# 2_PSU.net
KiCad netlist of a schematic drawn in Altium Designer
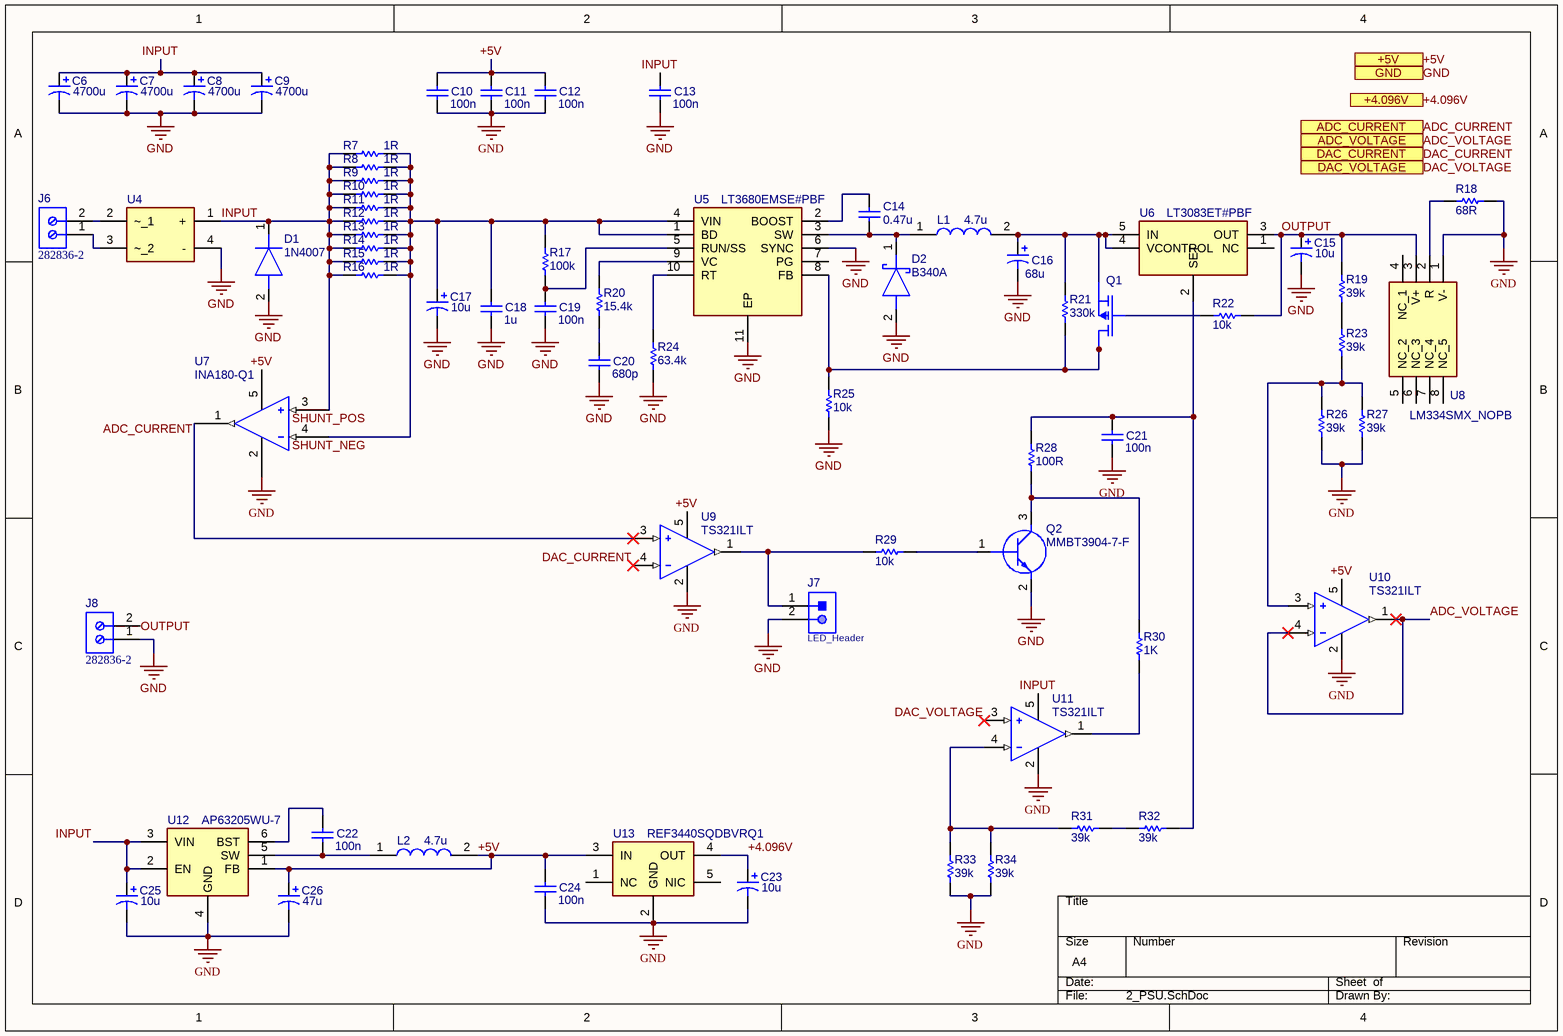
[diagram p0: 2_PSU.SchDoc]

(export (version "E")
  (design (tool "Eeschema 10.0.6"))
  (components
    (comp (ref "C6")
      (value "4700u")
      (footprint "CAPPRD750W80D1850H4150")
      (description "Polarized Capacitor (Radial)")
      (fields (field (name "Comment") "Cap Pol1") (field (name "PUBLISHER") "Altium Limited"))
      (libsource (lib "Miscellaneous Devices") (part "Cap Pol1"))
    )
    (comp (ref "C7")
      (value "4700u")
      (footprint "CAPPRD750W80D1850H4150")
      (description "Polarized Capacitor (Radial)")
      (fields (field (name "Comment") "Cap Pol1") (field (name "PUBLISHER") "Altium Limited"))
      (libsource (lib "Miscellaneous Devices") (part "Cap Pol1"))
    )
    (comp (ref "C8")
      (value "4700u")
      (footprint "CAPPRD750W80D1850H4150")
      (description "Polarized Capacitor (Radial)")
      (fields (field (name "Comment") "Cap Pol1") (field (name "PUBLISHER") "Altium Limited"))
      (libsource (lib "Miscellaneous Devices") (part "Cap Pol1"))
    )
    (comp (ref "C9")
      (value "4700u")
      (footprint "CAPPRD750W80D1850H4150")
      (description "Polarized Capacitor (Radial)")
      (fields (field (name "Comment") "Cap Pol1") (field (name "PUBLISHER") "Altium Limited"))
      (libsource (lib "Miscellaneous Devices") (part "Cap Pol1"))
    )
    (comp (ref "C10")
      (value "100n")
      (footprint "6-0805_N")
      (description "Capacitor")
      (libsource (lib "Simulation Generic Components") (part "Capacitor"))
    )
    (comp (ref "C11")
      (value "100n")
      (footprint "6-0805_N")
      (description "Capacitor")
      (libsource (lib "Simulation Generic Components") (part "Capacitor"))
    )
    (comp (ref "C12")
      (value "100n")
      (footprint "6-0805_N")
      (description "Capacitor")
      (libsource (lib "Simulation Generic Components") (part "Capacitor"))
    )
    (comp (ref "C13")
      (value "100n")
      (footprint "6-0805_N")
      (description "Capacitor")
      (libsource (lib "Simulation Generic Components") (part "Capacitor"))
    )
    (comp (ref "C14")
      (value "0.47u")
      (footprint "6-0805_N")
      (description "Capacitor")
      (libsource (lib "Simulation Generic Components") (part "Capacitor"))
    )
    (comp (ref "C15")
      (value "10u")
      (footprint "CAPPRD200W52D500H1250")
      (description "Polarized Capacitor (Radial)")
      (fields (field (name "Comment") "Cap Pol1") (field (name "PUBLISHER") "Altium Limited"))
      (libsource (lib "Miscellaneous Devices") (part "Cap Pol1"))
    )
    (comp (ref "C16")
      (value "68u")
      (footprint "CAPPRD250W52D630H1100")
      (description "Polarized Capacitor (Radial)")
      (fields (field (name "Comment") "Cap Pol1") (field (name "PUBLISHER") "Altium Limited"))
      (libsource (lib "Miscellaneous Devices") (part "Cap Pol1"))
    )
    (comp (ref "C17")
      (value "10u")
      (footprint "CAPPRD200W52D500H1250")
      (description "Polarized Capacitor (Radial)")
      (fields (field (name "Comment") "Cap Pol1") (field (name "PUBLISHER") "Altium Limited"))
      (libsource (lib "Miscellaneous Devices") (part "Cap Pol1"))
    )
    (comp (ref "C18")
      (value "1u")
      (footprint "6-0805_N")
      (description "Capacitor")
      (libsource (lib "Simulation Generic Components") (part "Capacitor"))
    )
    (comp (ref "C19")
      (value "100n")
      (footprint "6-0805_N")
      (description "Capacitor")
      (libsource (lib "Simulation Generic Components") (part "Capacitor"))
    )
    (comp (ref "C20")
      (value "680p")
      (footprint "6-0805_N")
      (description "Capacitor")
      (libsource (lib "Simulation Generic Components") (part "Capacitor"))
    )
    (comp (ref "C21")
      (value "100n")
      (footprint "6-0805_N")
      (description "Capacitor")
      (libsource (lib "Simulation Generic Components") (part "Capacitor"))
    )
    (comp (ref "C22")
      (value "100n")
      (footprint "6-0805_N")
      (description "Capacitor")
      (libsource (lib "Simulation Generic Components") (part "Capacitor"))
    )
    (comp (ref "C23")
      (value "10u")
      (footprint "CAPPRD200W52D500H1250")
      (description "Polarized Capacitor (Radial)")
      (fields (field (name "Comment") "Cap Pol1") (field (name "PUBLISHER") "Altium Limited"))
      (libsource (lib "Miscellaneous Devices") (part "Cap Pol1"))
    )
    (comp (ref "C24")
      (value "100n")
      (footprint "6-0805_N")
      (description "Capacitor")
      (libsource (lib "Simulation Generic Components") (part "Capacitor"))
    )
    (comp (ref "C25")
      (value "10u")
      (footprint "CAPPRD200W52D500H1250")
      (description "Polarized Capacitor (Radial)")
      (fields (field (name "Comment") "Cap Pol1") (field (name "PUBLISHER") "Altium Limited"))
      (libsource (lib "Miscellaneous Devices") (part "Cap Pol1"))
    )
    (comp (ref "C26")
      (value "47u")
      (footprint "CAPPRD200W52D500H1250")
      (description "Polarized Capacitor (Radial)")
      (fields (field (name "Comment") "Cap Pol1") (field (name "PUBLISHER") "Altium Limited"))
      (libsource (lib "Miscellaneous Devices") (part "Cap Pol1"))
    )
    (comp (ref "D1")
      (value "1N4007")
      (footprint "DIOAD1405W58L465D235")
      (description "Diode")
      (fields (field (name "MOUSER PART NUMBER") "637-1N4007"))
      (libsource (lib "PowerSupplyPE") (part "1N4007"))
    )
    (comp (ref "D2")
      (value "B340A")
      (footprint "DIOM5127X229N")
      (description "Diode")
      (fields
        (field (name "MANUFACTURER_PART_NUMBER") "B340A-E3/61T")
        (field (name "MOUSER PART NUMBER") "625-BD340A-E3/61T")
      )
      (libsource (lib "PowerSupplyPE") (part "B340A-E3_61T"))
    )
    (comp (ref "J6")
      (value "282836-2")
      (footprint "TECO-282836-2_V")
      (description "Female Header, Pitch 5 mm, 1 x 2 Position, Height 10 mm, Tail Length 3.5 mm, Rohs, Bulk")
      (fields (field (name "VOLTAGE") "300V") (field (name "MANUFACTURER") "TE Connectivity"))
      (libsource (lib "Altium Content Vault") (part "CN-1P-F-TB2"))
    )
    (comp (ref "J7")
      (value "LED_Header")
      (footprint "61300211121")
      (description "THT Vertical Pin Header WR-PHD, Pitch 2.54 mm, Single Row, 2 pins")
      (fields
        (field (name "MANUFACTURER") "Wurth Elektronik")
        (field (name "PART NUMBER") "61300211121")
        (field (name "PUBLISHER") "WurthElektronik")
      )
      (libsource (lib "Altium Content Vault") (part "WE-CN-1P-M-R2"))
    )
    (comp (ref "J8")
      (value "282836-2")
      (footprint "TECO-282836-2_V")
      (description "Female Header, Pitch 5 mm, 1 x 2 Position, Height 10 mm, Tail Length 3.5 mm, Rohs, Bulk")
      (fields (field (name "VOLTAGE") "300V") (field (name "MANUFACTURER") "TE Connectivity"))
      (libsource (lib "Altium Content Vault") (part "CN-1P-F-TB2"))
    )
    (comp (ref "L1")
      (value "4.7u")
      (footprint "VLS5045EX330M")
      (description "Inductor")
      (fields
        (field (name "MANUFACTURER_PART_NUMBER") "VLS5045EX-4R7M-H")
        (field (name "MOUSER PART NUMBER") "810-VLS5045EX-4R7M-H")
      )
      (libsource (lib "PowerSupplyPE") (part "VLS5045EX-4R7M-H"))
    )
    (comp (ref "L2")
      (value "4.7u")
      (footprint "VLS5045EX330M")
      (description "Inductor")
      (fields
        (field (name "MANUFACTURER_PART_NUMBER") "VLS5045EX-4R7M-H")
        (field (name "MOUSER PART NUMBER") "810-VLS5045EX-4R7M-H")
      )
      (libsource (lib "PowerSupplyPE") (part "VLS5045EX-4R7M-H"))
    )
    (comp (ref "Q1")
      (value "ZVP4525GTA")
      (footprint "SOT230P700X180-4N")
      (description "MOSFET (P-Channel)")
      (fields (field (name "MOUSER PART NUMBER") "522-ZVP4525GTA"))
      (libsource (lib "PowerSupplyPE") (part "ZVP4525GTA"))
    )
    (comp (ref "Q2")
      (value "MMBT3904-7-F")
      (footprint "SOT96P240X110-3N")
      (description "Transistor BJT NPN")
      (fields (field (name "MOUSER PART NUMBER") "621-MMBT3904-F"))
      (libsource (lib "*") (part "MMBT3904-7-F"))
    )
    (comp (ref "R7")
      (value "1R")
      (footprint "6-0805_N")
      (description "Resistor")
      (libsource (lib "Simulation Generic Components") (part "Resistor"))
    )
    (comp (ref "R8")
      (value "1R")
      (footprint "6-0805_N")
      (description "Resistor")
      (libsource (lib "Simulation Generic Components") (part "Resistor"))
    )
    (comp (ref "R9")
      (value "1R")
      (footprint "6-0805_N")
      (description "Resistor")
      (libsource (lib "Simulation Generic Components") (part "Resistor"))
    )
    (comp (ref "R10")
      (value "1R")
      (footprint "6-0805_N")
      (description "Resistor")
      (libsource (lib "Simulation Generic Components") (part "Resistor"))
    )
    (comp (ref "R11")
      (value "1R")
      (footprint "6-0805_N")
      (description "Resistor")
      (libsource (lib "Simulation Generic Components") (part "Resistor"))
    )
    (comp (ref "R12")
      (value "1R")
      (footprint "6-0805_N")
      (description "Resistor")
      (libsource (lib "Simulation Generic Components") (part "Resistor"))
    )
    (comp (ref "R13")
      (value "1R")
      (footprint "6-0805_N")
      (description "Resistor")
      (libsource (lib "Simulation Generic Components") (part "Resistor"))
    )
    (comp (ref "R14")
      (value "1R")
      (footprint "6-0805_N")
      (description "Resistor")
      (libsource (lib "Simulation Generic Components") (part "Resistor"))
    )
    (comp (ref "R15")
      (value "1R")
      (footprint "6-0805_N")
      (description "Resistor")
      (libsource (lib "Simulation Generic Components") (part "Resistor"))
    )
    (comp (ref "R16")
      (value "1R")
      (footprint "6-0805_N")
      (description "Resistor")
      (libsource (lib "Simulation Generic Components") (part "Resistor"))
    )
    (comp (ref "R17")
      (value "100k")
      (footprint "6-0805_N")
      (description "Resistor")
      (libsource (lib "Simulation Generic Components") (part "Resistor"))
    )
    (comp (ref "R18")
      (value "68R")
      (footprint "6-0805_N")
      (description "Resistor")
      (libsource (lib "Simulation Generic Components") (part "Resistor"))
    )
    (comp (ref "R19")
      (value "39k")
      (footprint "6-0805_N")
      (description "Resistor")
      (libsource (lib "Simulation Generic Components") (part "Resistor"))
    )
    (comp (ref "R20")
      (value "15.4k")
      (footprint "6-0805_N")
      (description "Resistor")
      (libsource (lib "Simulation Generic Components") (part "Resistor"))
    )
    (comp (ref "R21")
      (value "330k")
      (footprint "6-0805_N")
      (description "Resistor")
      (libsource (lib "Simulation Generic Components") (part "Resistor"))
    )
    (comp (ref "R22")
      (value "10k")
      (footprint "6-0805_N")
      (description "Resistor")
      (libsource (lib "Simulation Generic Components") (part "Resistor"))
    )
    (comp (ref "R23")
      (value "39k")
      (footprint "6-0805_N")
      (description "Resistor")
      (libsource (lib "Simulation Generic Components") (part "Resistor"))
    )
    (comp (ref "R24")
      (value "63.4k")
      (footprint "6-0805_N")
      (description "Resistor")
      (libsource (lib "Simulation Generic Components") (part "Resistor"))
    )
    (comp (ref "R25")
      (value "10k")
      (footprint "6-0805_N")
      (description "Resistor")
      (libsource (lib "Simulation Generic Components") (part "Resistor"))
    )
    (comp (ref "R26")
      (value "39k")
      (footprint "6-0805_N")
      (description "Resistor")
      (libsource (lib "Simulation Generic Components") (part "Resistor"))
    )
    (comp (ref "R27")
      (value "39k")
      (footprint "6-0805_N")
      (description "Resistor")
      (libsource (lib "Simulation Generic Components") (part "Resistor"))
    )
    (comp (ref "R28")
      (value "100R")
      (footprint "6-0805_N")
      (description "Resistor")
      (libsource (lib "Simulation Generic Components") (part "Resistor"))
    )
    (comp (ref "R29")
      (value "10k")
      (footprint "6-0805_N")
      (description "Resistor")
      (libsource (lib "Simulation Generic Components") (part "Resistor"))
    )
    (comp (ref "R30")
      (value "1K")
      (footprint "6-0805_N")
      (description "Resistor")
      (libsource (lib "Simulation Generic Components") (part "Resistor"))
    )
    (comp (ref "R31")
      (value "39k")
      (footprint "6-0805_N")
      (description "Resistor")
      (libsource (lib "Simulation Generic Components") (part "Resistor"))
    )
    (comp (ref "R32")
      (value "39k")
      (footprint "6-0805_N")
      (description "Resistor")
      (libsource (lib "Simulation Generic Components") (part "Resistor"))
    )
    (comp (ref "R33")
      (value "39k")
      (footprint "6-0805_N")
      (description "Resistor")
      (libsource (lib "Simulation Generic Components") (part "Resistor"))
    )
    (comp (ref "R34")
      (value "39k")
      (footprint "6-0805_N")
      (description "Resistor")
      (libsource (lib "Simulation Generic Components") (part "Resistor"))
    )
    (comp (ref "U4")
      (value "GBU1010_T0_00601")
      (footprint "GBU1010_T0_00601")
      (description "Bridge Rectifier")
      (fields (field (name "MOUSER PART NUMBER") "241-GBU1010_T0_00601"))
      (libsource (lib "PowerSupplyPE") (part "GBU1010_T0_00601"))
    )
    (comp (ref "U5")
      (value "LT3680EMSE#PBF")
      (footprint "SOP50P490X110-11N")
      (description "Integrated Circuit")
      (fields (field (name "MOUSER PART NUMBER") "584-LT3680EMSE#PBF"))
      (libsource (lib "PowerSupplyPE") (part "LT3680EMSE#PBF"))
    )
    (comp (ref "U6")
      (value "LT3083ET#PBF")
      (footprint "TO170P457X1022X2306-5P")
      (description "Integrated Circuit")
      (fields (field (name "MOUSER PART NUMBER") "584-LT3083ET#PBF"))
      (libsource (lib "PowerSupplyPE") (part "LT3083ET#PBF"))
    )
    (comp (ref "U7")
      (value "INA180-Q1")
      (footprint "SOT95P280X145-5N")
      (description "Current Sense Amplifier")
      (libsource (lib "PowerSupplyPE") (part "INA180-Q1"))
    )
    (comp (ref "U8")
      (value "LM334SMX_NOPB")
      (footprint "SOIC127P600X175-8N")
      (description "Integrated Circuit")
      (fields
        (field (name "MANUFACTURER_PART_NUMBER") "LM334SMX/NOPB")
        (field (name "MOUSER PART NUMBER") "926-LM334SMX/NOPB")
      )
      (libsource (lib "PowerSupplyPE") (part "LM334SMX_NOPB"))
    )
    (comp (ref "U9")
      (value "TS321ILT")
      (footprint "SOT95P280X145-5N")
      (description "Integrated Circuit")
      (fields (field (name "MOUSER PART NUMBER") "511-TS321IL"))
      (libsource (lib "PowerSupplyPE") (part "TS321ILT"))
    )
    (comp (ref "U10")
      (value "TS321ILT")
      (footprint "SOT95P280X145-5N")
      (description "Integrated Circuit")
      (fields (field (name "MOUSER PART NUMBER") "511-TS321IL"))
      (libsource (lib "PowerSupplyPE") (part "TS321ILT"))
    )
    (comp (ref "U11")
      (value "TS321ILT")
      (footprint "SOT95P280X145-5N")
      (description "Integrated Circuit")
      (fields (field (name "MOUSER PART NUMBER") "511-TS321IL"))
      (libsource (lib "PowerSupplyPE") (part "TS321ILT"))
    )
    (comp (ref "U12")
      (value "AP63205WU-7")
      (footprint "SOT95P280X100-6N")
      (description "Integrated Circuit")
      (fields (field (name "MOUSER PART NUMBER") "621-AP63205WU-7"))
      (libsource (lib "PowerSupplyPE") (part "AP63205WU-7"))
    )
    (comp (ref "U13")
      (value "REF3440SQDBVRQ1")
      (footprint "SOT95P280X145-5N")
      (description "Integrated Circuit")
      (fields (field (name "MOUSER PART NUMBER") "595-REF3440SQDBVRQ1"))
      (libsource (lib "PowerSupplyPE") (part "REF3440SQDBVRQ1"))
    )
  )
  (nets
    (net (code "1") (name "/+4.096V") (class "Default")
      (node (ref "C23") (pin "1") (pinfunction "1_1") (pintype "passive"))
      (node (ref "U13") (pin "4") (pinfunction "OUT_4") (pintype "passive"))
    )
    (net (code "2") (name "/+5V") (class "Default")
      (node (ref "C10") (pin "2") (pinfunction "2_2") (pintype "passive"))
      (node (ref "C11") (pin "2") (pinfunction "2_2") (pintype "passive"))
      (node (ref "C12") (pin "2") (pinfunction "2_2") (pintype "passive"))
      (node (ref "C24") (pin "2") (pinfunction "2_2") (pintype "passive"))
      (node (ref "C26") (pin "1") (pinfunction "1_1") (pintype "passive"))
      (node (ref "L2") (pin "2") (pinfunction "2_2") (pintype "passive"))
      (node (ref "U10") (pin "5") (pinfunction "VCC+_5") (pintype "power_in"))
      (node (ref "U12") (pin "1") (pinfunction "FB_1") (pintype "passive"))
      (node (ref "U13") (pin "3") (pinfunction "IN_3") (pintype "passive"))
      (node (ref "U7") (pin "5") (pinfunction "VS_5") (pintype "power_in"))
      (node (ref "U9") (pin "5") (pinfunction "VCC+_5") (pintype "power_in"))
    )
    (net (code "3") (name "/ADC_CURRENT") (class "Default")
      (node (ref "U7") (pin "1") (pinfunction "OUT_1") (pintype "output"))
      (node (ref "U9") (pin "3") (pinfunction "NON-INVERTING_INPUT_3") (pintype "input"))
    )
    (net (code "4") (name "/ADC_VOLTAGE") (class "Default")
      (node (ref "U10") (pin "1") (pinfunction "OUTPUT_1") (pintype "output"))
      (node (ref "U10") (pin "4") (pinfunction "INVERTING_INPUT_4") (pintype "input"))
    )
    (net (code "5") (name "/DAC_CURRENT") (class "Default")
      (node (ref "U9") (pin "4") (pinfunction "INVERTING_INPUT_4") (pintype "input+no_connect"))
    )
    (net (code "6") (name "/DAC_VOLTAGE") (class "Default")
      (node (ref "U11") (pin "3") (pinfunction "NON-INVERTING_INPUT_3") (pintype "input+no_connect"))
    )
    (net (code "7") (name "/INPUT") (class "Default")
      (node (ref "C13") (pin "2") (pinfunction "2_2") (pintype "passive"))
      (node (ref "C25") (pin "1") (pinfunction "1_1") (pintype "passive"))
      (node (ref "C6") (pin "1") (pinfunction "1_1") (pintype "passive"))
      (node (ref "C7") (pin "1") (pinfunction "1_1") (pintype "passive"))
      (node (ref "C8") (pin "1") (pinfunction "1_1") (pintype "passive"))
      (node (ref "C9") (pin "1") (pinfunction "1_1") (pintype "passive"))
      (node (ref "D1") (pin "1") (pinfunction "K_1") (pintype "passive"))
      (node (ref "R10") (pin "1") (pinfunction "1_1") (pintype "passive"))
      (node (ref "R11") (pin "1") (pinfunction "1_1") (pintype "passive"))
      (node (ref "R12") (pin "1") (pinfunction "1_1") (pintype "passive"))
      (node (ref "R13") (pin "1") (pinfunction "1_1") (pintype "passive"))
      (node (ref "R14") (pin "1") (pinfunction "1_1") (pintype "passive"))
      (node (ref "R15") (pin "1") (pinfunction "1_1") (pintype "passive"))
      (node (ref "R16") (pin "1") (pinfunction "1_1") (pintype "passive"))
      (node (ref "R7") (pin "1") (pinfunction "1_1") (pintype "passive"))
      (node (ref "R8") (pin "1") (pinfunction "1_1") (pintype "passive"))
      (node (ref "R9") (pin "1") (pinfunction "1_1") (pintype "passive"))
      (node (ref "U11") (pin "5") (pinfunction "VCC+_5") (pintype "power_in"))
      (node (ref "U12") (pin "2") (pinfunction "EN_2") (pintype "passive"))
      (node (ref "U12") (pin "3") (pinfunction "VIN_3") (pintype "passive"))
      (node (ref "U4") (pin "1") (pinfunction "+_1") (pintype "passive"))
      (node (ref "U7") (pin "3") (pinfunction "IN+_3") (pintype "input"))
    )
    (net (code "8") (name "/OUTPUT") (class "Default")
      (node (ref "C15") (pin "1") (pinfunction "1_1") (pintype "passive"))
      (node (ref "J8") (pin "2") (pinfunction "2_2") (pintype "passive"))
      (node (ref "R19") (pin "2") (pinfunction "2_2") (pintype "passive"))
      (node (ref "R22") (pin "1") (pinfunction "1_1") (pintype "passive"))
      (node (ref "U6") (pin "3") (pinfunction "OUT_3") (pintype "passive"))
      (node (ref "U8") (pin "3") (pinfunction "V+_3") (pintype "passive"))
    )
    (net (code "9") (name "/SHUNT_NEG") (class "Default")
      (node (ref "C17") (pin "1") (pinfunction "1_1") (pintype "passive"))
      (node (ref "C18") (pin "2") (pinfunction "2_2") (pintype "passive"))
      (node (ref "R10") (pin "2") (pinfunction "2_2") (pintype "passive"))
      (node (ref "R11") (pin "2") (pinfunction "2_2") (pintype "passive"))
      (node (ref "R12") (pin "2") (pinfunction "2_2") (pintype "passive"))
      (node (ref "R13") (pin "2") (pinfunction "2_2") (pintype "passive"))
      (node (ref "R14") (pin "2") (pinfunction "2_2") (pintype "passive"))
      (node (ref "R15") (pin "2") (pinfunction "2_2") (pintype "passive"))
      (node (ref "R16") (pin "2") (pinfunction "2_2") (pintype "passive"))
      (node (ref "R17") (pin "2") (pinfunction "2_2") (pintype "passive"))
      (node (ref "R7") (pin "2") (pinfunction "2_2") (pintype "passive"))
      (node (ref "R8") (pin "2") (pinfunction "2_2") (pintype "passive"))
      (node (ref "R9") (pin "2") (pinfunction "2_2") (pintype "passive"))
      (node (ref "U5") (pin "1") (pinfunction "BD_1") (pintype "passive"))
      (node (ref "U5") (pin "4") (pinfunction "VIN_4") (pintype "passive"))
      (node (ref "U7") (pin "4") (pinfunction "IN-_4") (pintype "input"))
    )
    (net (code "10") (name "GND") (class "Default")
      (node (ref "C10") (pin "1") (pinfunction "1_1") (pintype "passive"))
      (node (ref "C11") (pin "1") (pinfunction "1_1") (pintype "passive"))
      (node (ref "C12") (pin "1") (pinfunction "1_1") (pintype "passive"))
      (node (ref "C13") (pin "1") (pinfunction "1_1") (pintype "passive"))
      (node (ref "C15") (pin "2") (pinfunction "2_2") (pintype "passive"))
      (node (ref "C16") (pin "2") (pinfunction "2_2") (pintype "passive"))
      (node (ref "C17") (pin "2") (pinfunction "2_2") (pintype "passive"))
      (node (ref "C18") (pin "1") (pinfunction "1_1") (pintype "passive"))
      (node (ref "C19") (pin "1") (pinfunction "1_1") (pintype "passive"))
      (node (ref "C20") (pin "1") (pinfunction "1_1") (pintype "passive"))
      (node (ref "C21") (pin "1") (pinfunction "1_1") (pintype "passive"))
      (node (ref "C23") (pin "2") (pinfunction "2_2") (pintype "passive"))
      (node (ref "C24") (pin "1") (pinfunction "1_1") (pintype "passive"))
      (node (ref "C25") (pin "2") (pinfunction "2_2") (pintype "passive"))
      (node (ref "C26") (pin "2") (pinfunction "2_2") (pintype "passive"))
      (node (ref "C6") (pin "2") (pinfunction "2_2") (pintype "passive"))
      (node (ref "C7") (pin "2") (pinfunction "2_2") (pintype "passive"))
      (node (ref "C8") (pin "2") (pinfunction "2_2") (pintype "passive"))
      (node (ref "C9") (pin "2") (pinfunction "2_2") (pintype "passive"))
      (node (ref "D1") (pin "2") (pinfunction "A_2") (pintype "passive"))
      (node (ref "D2") (pin "2") (pinfunction "A_2") (pintype "passive"))
      (node (ref "J7") (pin "2") (pinfunction "2_2") (pintype "passive"))
      (node (ref "J8") (pin "1") (pinfunction "1_1") (pintype "passive"))
      (node (ref "Q2") (pin "2") (pinfunction "E_2") (pintype "passive"))
      (node (ref "R18") (pin "1") (pinfunction "1_1") (pintype "passive"))
      (node (ref "R24") (pin "1") (pinfunction "1_1") (pintype "passive"))
      (node (ref "R25") (pin "1") (pinfunction "1_1") (pintype "passive"))
      (node (ref "R26") (pin "1") (pinfunction "1_1") (pintype "passive"))
      (node (ref "R27") (pin "1") (pinfunction "1_1") (pintype "passive"))
      (node (ref "R33") (pin "1") (pinfunction "1_1") (pintype "passive"))
      (node (ref "R34") (pin "1") (pinfunction "1_1") (pintype "passive"))
      (node (ref "U10") (pin "2") (pinfunction "VCC-_2") (pintype "power_in"))
      (node (ref "U11") (pin "2") (pinfunction "VCC-_2") (pintype "power_in"))
      (node (ref "U12") (pin "4") (pinfunction "GND_4") (pintype "passive"))
      (node (ref "U13") (pin "2") (pinfunction "GND_2") (pintype "passive"))
      (node (ref "U4") (pin "4") (pinfunction "-_4") (pintype "passive"))
      (node (ref "U5") (pin "11") (pinfunction "EP_11") (pintype "passive"))
      (node (ref "U5") (pin "6") (pinfunction "SYNC_6") (pintype "passive"))
      (node (ref "U7") (pin "2") (pinfunction "GND_2") (pintype "power_in"))
      (node (ref "U8") (pin "1") (pinfunction "V-_1") (pintype "passive"))
      (node (ref "U9") (pin "2") (pinfunction "VCC-_2") (pintype "power_in"))
    )
    (net (code "11") (name "Net-(C20-Pad2)") (class "Default")
      (node (ref "C20") (pin "2") (pinfunction "2_2") (pintype "passive"))
      (node (ref "R20") (pin "1") (pinfunction "1_1") (pintype "passive"))
    )
    (net (code "12") (name "Net-(D2-K)") (class "Default")
      (node (ref "C14") (pin "1") (pinfunction "1_1") (pintype "passive"))
      (node (ref "D2") (pin "1") (pinfunction "K_1") (pintype "passive"))
      (node (ref "L1") (pin "1") (pinfunction "1_1") (pintype "passive"))
      (node (ref "U5") (pin "3") (pinfunction "SW_3") (pintype "passive"))
    )
    (net (code "13") (name "Net-(Q1-D_1)") (class "Default")
      (node (ref "Q1") (pin "2") (pinfunction "D_1_2") (pintype "passive"))
      (node (ref "Q1") (pin "4") (pinfunction "D_2_4") (pintype "passive"))
      (node (ref "R21") (pin "1") (pinfunction "1_1") (pintype "passive"))
      (node (ref "R25") (pin "2") (pinfunction "2_2") (pintype "passive"))
      (node (ref "U5") (pin "8") (pinfunction "FB_8") (pintype "passive"))
    )
    (net (code "14") (name "Net-(Q1-G)") (class "Default")
      (node (ref "Q1") (pin "1") (pinfunction "G_1") (pintype "passive"))
      (node (ref "R22") (pin "2") (pinfunction "2_2") (pintype "passive"))
    )
    (net (code "15") (name "Net-(Q1-S)") (class "Default")
      (node (ref "C16") (pin "1") (pinfunction "1_1") (pintype "passive"))
      (node (ref "L1") (pin "2") (pinfunction "2_2") (pintype "passive"))
      (node (ref "Q1") (pin "3") (pinfunction "S_3") (pintype "passive"))
      (node (ref "R21") (pin "2") (pinfunction "2_2") (pintype "passive"))
      (node (ref "U6") (pin "4") (pinfunction "VCONTROL_4") (pintype "passive"))
      (node (ref "U6") (pin "5") (pinfunction "IN_5") (pintype "passive"))
    )
    (net (code "16") (name "Net-(Q2-B)") (class "Default")
      (node (ref "Q2") (pin "1") (pinfunction "B_1") (pintype "passive"))
      (node (ref "R29") (pin "2") (pinfunction "2_2") (pintype "passive"))
    )
    (net (code "17") (name "Net-(Q2-C)") (class "Default")
      (node (ref "Q2") (pin "3") (pinfunction "C_3") (pintype "passive"))
      (node (ref "R28") (pin "1") (pinfunction "1_1") (pintype "passive"))
      (node (ref "R30") (pin "2") (pinfunction "2_2") (pintype "passive"))
    )
    (net (code "18") (name "Net-(R19-Pad1)") (class "Default")
      (node (ref "R19") (pin "1") (pinfunction "1_1") (pintype "passive"))
      (node (ref "R23") (pin "2") (pinfunction "2_2") (pintype "passive"))
    )
    (net (code "19") (name "Net-(R31-Pad1)") (class "Default")
      (node (ref "R31") (pin "1") (pinfunction "1_1") (pintype "passive"))
      (node (ref "R32") (pin "2") (pinfunction "2_2") (pintype "passive"))
    )
    (net (code "20") (name "Net-(U4-~_1)") (class "Default")
      (node (ref "J6") (pin "2") (pinfunction "2_2") (pintype "passive"))
      (node (ref "U4") (pin "2") (pinfunction "~_1_2") (pintype "passive"))
    )
    (net (code "21") (name "Net-(U4-~_2)") (class "Default")
      (node (ref "J6") (pin "1") (pinfunction "1_1") (pintype "passive"))
      (node (ref "U4") (pin "3") (pinfunction "~_2_3") (pintype "passive"))
    )
    (net (code "22") (name "Net-(U5-BOOST)") (class "Default")
      (node (ref "C14") (pin "2") (pinfunction "2_2") (pintype "passive"))
      (node (ref "U5") (pin "2") (pinfunction "BOOST_2") (pintype "passive"))
    )
    (net (code "23") (name "Net-(U5-RT)") (class "Default")
      (node (ref "R24") (pin "2") (pinfunction "2_2") (pintype "passive"))
      (node (ref "U5") (pin "10") (pinfunction "RT_10") (pintype "passive"))
    )
    (net (code "24") (name "Net-(U5-RUN{slash}SS)") (class "Default")
      (node (ref "C19") (pin "2") (pinfunction "2_2") (pintype "passive"))
      (node (ref "R17") (pin "1") (pinfunction "1_1") (pintype "passive"))
      (node (ref "U5") (pin "5") (pinfunction "RUN/SS_5") (pintype "passive"))
    )
    (net (code "25") (name "Net-(U5-VC)") (class "Default")
      (node (ref "R20") (pin "2") (pinfunction "2_2") (pintype "passive"))
      (node (ref "U5") (pin "9") (pinfunction "VC_9") (pintype "passive"))
    )
    (net (code "26") (name "Net-(U6-SET)") (class "Default")
      (node (ref "C21") (pin "2") (pinfunction "2_2") (pintype "passive"))
      (node (ref "R28") (pin "2") (pinfunction "2_2") (pintype "passive"))
      (node (ref "R32") (pin "1") (pinfunction "1_1") (pintype "passive"))
      (node (ref "U6") (pin "2") (pinfunction "SET_2") (pintype "passive"))
    )
    (net (code "27") (name "Net-(U8-R)") (class "Default")
      (node (ref "R18") (pin "2") (pinfunction "2_2") (pintype "passive"))
      (node (ref "U8") (pin "2") (pinfunction "R_2") (pintype "passive"))
    )
    (net (code "28") (name "Net-(U9-OUTPUT)") (class "Default")
      (node (ref "J7") (pin "1") (pinfunction "1_1") (pintype "passive"))
      (node (ref "R29") (pin "1") (pinfunction "1_1") (pintype "passive"))
      (node (ref "U9") (pin "1") (pinfunction "OUTPUT_1") (pintype "output"))
    )
    (net (code "29") (name "Net-(U10-NON-INVERTING_INPUT)") (class "Default")
      (node (ref "R23") (pin "1") (pinfunction "1_1") (pintype "passive"))
      (node (ref "R26") (pin "2") (pinfunction "2_2") (pintype "passive"))
      (node (ref "R27") (pin "2") (pinfunction "2_2") (pintype "passive"))
      (node (ref "U10") (pin "3") (pinfunction "NON-INVERTING_INPUT_3") (pintype "input"))
    )
    (net (code "30") (name "Net-(U11-INVERTING_INPUT)") (class "Default")
      (node (ref "R31") (pin "2") (pinfunction "2_2") (pintype "passive"))
      (node (ref "R33") (pin "2") (pinfunction "2_2") (pintype "passive"))
      (node (ref "R34") (pin "2") (pinfunction "2_2") (pintype "passive"))
      (node (ref "U11") (pin "4") (pinfunction "INVERTING_INPUT_4") (pintype "input"))
    )
    (net (code "31") (name "Net-(U11-OUTPUT)") (class "Default")
      (node (ref "R30") (pin "1") (pinfunction "1_1") (pintype "passive"))
      (node (ref "U11") (pin "1") (pinfunction "OUTPUT_1") (pintype "output"))
    )
    (net (code "32") (name "Net-(U12-BST)") (class "Default")
      (node (ref "C22") (pin "2") (pinfunction "2_2") (pintype "passive"))
      (node (ref "U12") (pin "6") (pinfunction "BST_6") (pintype "passive"))
    )
    (net (code "33") (name "Net-(U12-SW)") (class "Default")
      (node (ref "C22") (pin "1") (pinfunction "1_1") (pintype "passive"))
      (node (ref "L2") (pin "1") (pinfunction "1_1") (pintype "passive"))
      (node (ref "U12") (pin "5") (pinfunction "SW_5") (pintype "passive"))
    )
    (net (code "34") (name "unconnected-(U5-PG-Pad7)") (class "Default")
      (node (ref "U5") (pin "7") (pinfunction "PG_7") (pintype "passive"))
    )
    (net (code "35") (name "unconnected-(U6-NC-Pad1)") (class "Default")
      (node (ref "U6") (pin "1") (pinfunction "NC_1") (pintype "passive"))
    )
    (net (code "36") (name "unconnected-(U8-NC_1-Pad4)") (class "Default")
      (node (ref "U8") (pin "4") (pinfunction "NC_1_4") (pintype "passive"))
    )
    (net (code "37") (name "unconnected-(U8-NC_2-Pad5)") (class "Default")
      (node (ref "U8") (pin "5") (pinfunction "NC_2_5") (pintype "passive"))
    )
    (net (code "38") (name "unconnected-(U8-NC_3-Pad6)") (class "Default")
      (node (ref "U8") (pin "6") (pinfunction "NC_3_6") (pintype "passive"))
    )
    (net (code "39") (name "unconnected-(U8-NC_4-Pad7)") (class "Default")
      (node (ref "U8") (pin "7") (pinfunction "NC_4_7") (pintype "passive"))
    )
    (net (code "40") (name "unconnected-(U8-NC_5-Pad8)") (class "Default")
      (node (ref "U8") (pin "8") (pinfunction "NC_5_8") (pintype "passive"))
    )
    (net (code "41") (name "unconnected-(U13-NC-Pad1)") (class "Default")
      (node (ref "U13") (pin "1") (pinfunction "NC_1") (pintype "passive"))
    )
    (net (code "42") (name "unconnected-(U13-NIC-Pad5)") (class "Default")
      (node (ref "U13") (pin "5") (pinfunction "NIC_5") (pintype "passive"))
    )
  )
)
